# ldo.net
KiCad netlist of a schematic drawn in EAGLE
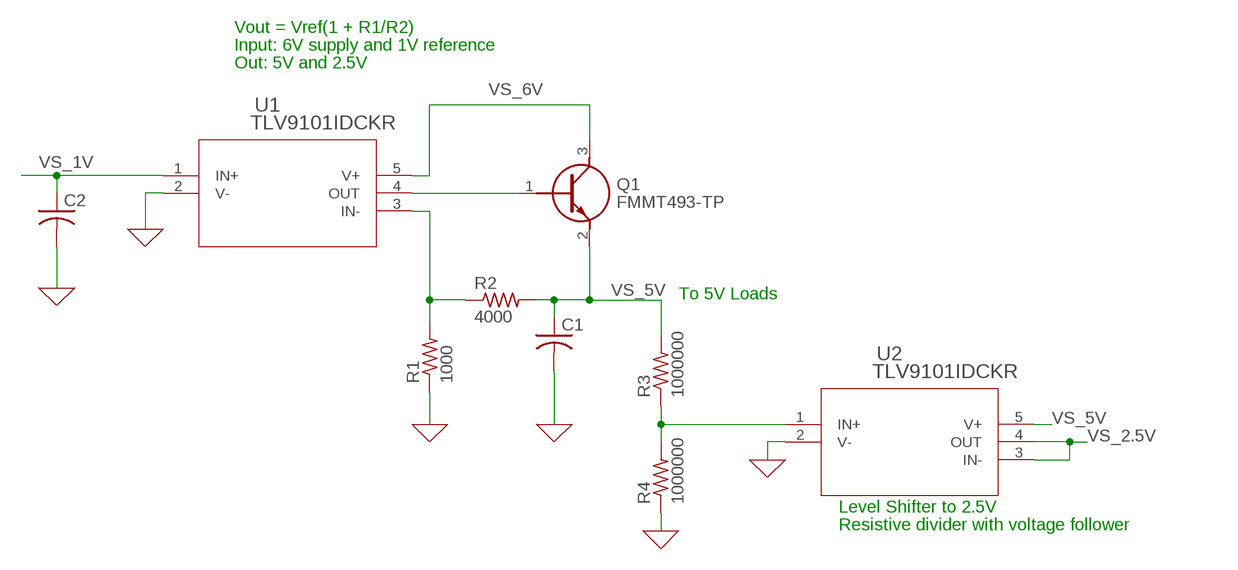
[diagram p0: schematic, sheet 1]

(export (version "E")
  (design (tool "Eeschema 10.0.6"))
  (components
    (comp (ref "C1")
      (value "C-USC0603")
      (footprint "eagle-import:C0603")
      (libsource (lib "eagle-import") (part "C-USC0603"))
    )
    (comp (ref "C2")
      (value "C-USC0603")
      (footprint "eagle-import:C0603")
      (libsource (lib "eagle-import") (part "C-USC0603"))
    )
    (comp (ref "Q1")
      (value "FMMT493-TP")
      (footprint "eagle-import:SOT95P237X125-3N")
      (fields (field (name "MOUSER_PART_NUMBER") "833-FMMT493-TP"))
      (libsource (lib "eagle-import") (part "FMMT493-TP"))
    )
    (comp (ref "R1")
      (value "1000")
      (footprint "eagle-import:R0603")
      (libsource (lib "eagle-import") (part "R-US_R0603"))
    )
    (comp (ref "R2")
      (value "4000")
      (footprint "eagle-import:R0603")
      (libsource (lib "eagle-import") (part "R-US_R0603"))
    )
    (comp (ref "R3")
      (value "1000000")
      (footprint "eagle-import:R0603")
      (libsource (lib "eagle-import") (part "R-US_R0603"))
    )
    (comp (ref "R4")
      (value "1000000")
      (footprint "eagle-import:R0603")
      (libsource (lib "eagle-import") (part "R-US_R0603"))
    )
    (comp (ref "U1")
      (value "TLV9101IDCKR")
      (footprint "eagle-import:SC70-5_DCK_TEX")
      (fields (field (name "COPYRIGHT") "Copyright (C) 2024 Ultra Librarian. All rights reserved."))
      (libsource (lib "eagle-import") (part "TLV9101IDCKR"))
    )
    (comp (ref "U2")
      (value "TLV9101IDCKR")
      (footprint "eagle-import:SC70-5_DCK_TEX")
      (fields (field (name "COPYRIGHT") "Copyright (C) 2024 Ultra Librarian. All rights reserved."))
      (libsource (lib "eagle-import") (part "TLV9101IDCKR"))
    )
  )
  (nets
    (net (code "1") (name "/VS_1V") (class "Default")
      (node (ref "C2") (pin "1") (pinfunction "1_1") (pintype "passive"))
      (node (ref "U1") (pin "1") (pinfunction "IN+_1") (pintype "input"))
    )
    (net (code "2") (name "/VS_2.5V") (class "Default")
      (node (ref "U2") (pin "3") (pinfunction "IN-_3") (pintype "input"))
      (node (ref "U2") (pin "4") (pinfunction "OUT_4") (pintype "output"))
    )
    (net (code "3") (name "/VS_5V") (class "Default")
      (node (ref "C1") (pin "1") (pinfunction "1_1") (pintype "passive"))
      (node (ref "Q1") (pin "2") (pinfunction "E_2") (pintype "bidirectional"))
      (node (ref "R2") (pin "2") (pinfunction "2_2") (pintype "passive"))
      (node (ref "R3") (pin "2") (pinfunction "2_2") (pintype "passive"))
      (node (ref "U2") (pin "5") (pinfunction "V+_5") (pintype "power_in"))
    )
    (net (code "4") (name "/VS_6V") (class "Default")
      (node (ref "Q1") (pin "3") (pinfunction "C_3") (pintype "bidirectional"))
      (node (ref "U1") (pin "5") (pinfunction "V+_5") (pintype "power_in"))
    )
    (net (code "5") (name "GND") (class "Default")
      (node (ref "C1") (pin "2") (pinfunction "2_2") (pintype "passive"))
      (node (ref "C2") (pin "2") (pinfunction "2_2") (pintype "passive"))
      (node (ref "R1") (pin "1") (pinfunction "1_1") (pintype "passive"))
      (node (ref "R4") (pin "1") (pinfunction "1_1") (pintype "passive"))
      (node (ref "U1") (pin "2") (pinfunction "V-_2") (pintype "power_in"))
      (node (ref "U2") (pin "2") (pinfunction "V-_2") (pintype "power_in"))
    )
    (net (code "6") (name "Net-(Q1-B)") (class "Default")
      (node (ref "Q1") (pin "1") (pinfunction "B_1") (pintype "bidirectional"))
      (node (ref "U1") (pin "4") (pinfunction "OUT_4") (pintype "output"))
    )
    (net (code "7") (name "Net-(U1-IN-)") (class "Default")
      (node (ref "R1") (pin "2") (pinfunction "2_2") (pintype "passive"))
      (node (ref "R2") (pin "1") (pinfunction "1_1") (pintype "passive"))
      (node (ref "U1") (pin "3") (pinfunction "IN-_3") (pintype "input"))
    )
    (net (code "8") (name "Net-(U2-IN+)") (class "Default")
      (node (ref "R3") (pin "1") (pinfunction "1_1") (pintype "passive"))
      (node (ref "R4") (pin "2") (pinfunction "2_2") (pintype "passive"))
      (node (ref "U2") (pin "1") (pinfunction "IN+_1") (pintype "input"))
    )
  )
)
